# gforce_single_board.net
KiCad netlist of a schematic drawn in EAGLE
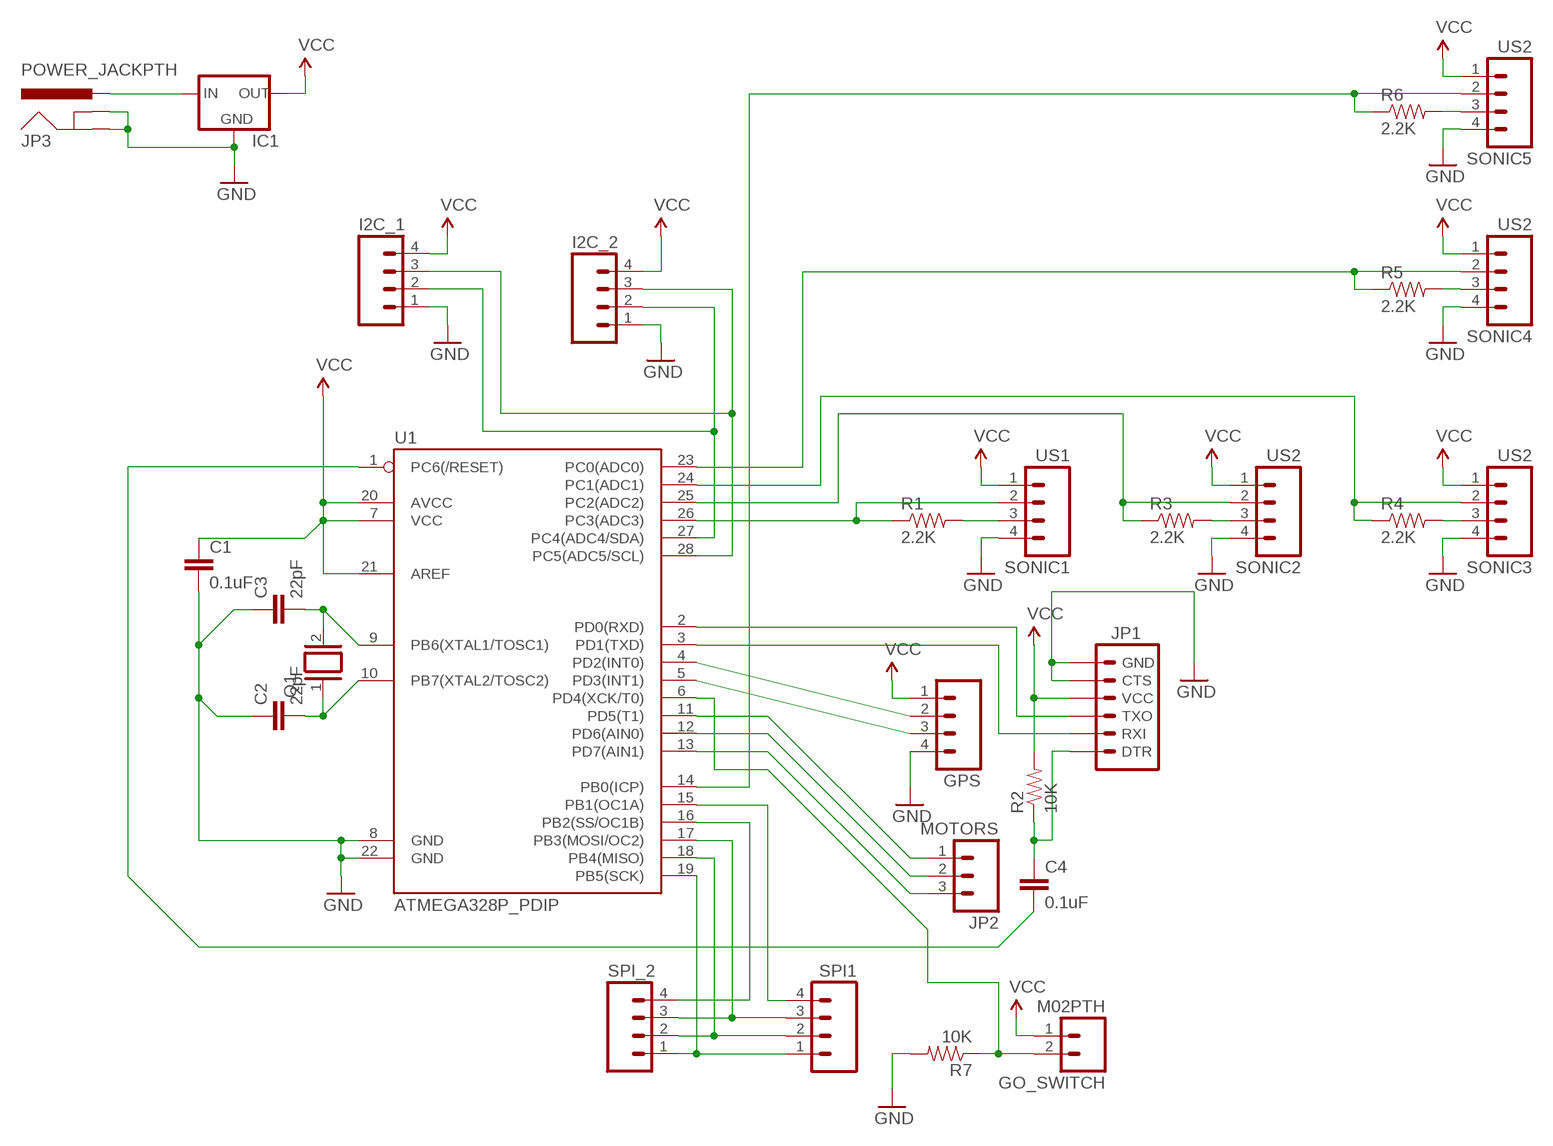
[diagram p0: schematic, sheet 1]

(export (version "E")
  (design (tool "Eeschema 10.0.6"))
  (components
    (comp (ref "C1")
      (value "0.1uF")
      (footprint "eagle-import:CAP-PTH-SMALL")
      (libsource (lib "eagle-import") (part "CAPPTH"))
    )
    (comp (ref "C2")
      (value "22pF")
      (footprint "eagle-import:CAP-PTH-SMALL")
      (libsource (lib "eagle-import") (part "CAPPTH"))
    )
    (comp (ref "C3")
      (value "22pF")
      (footprint "eagle-import:CAP-PTH-SMALL")
      (libsource (lib "eagle-import") (part "CAPPTH"))
    )
    (comp (ref "C4")
      (value "0.1uF")
      (footprint "eagle-import:CAP-PTH-SMALL")
      (libsource (lib "eagle-import") (part "CAPPTH"))
    )
    (comp (ref "GO_SWITCH")
      (value "M02PTH")
      (footprint "eagle-import:1X02")
      (libsource (lib "eagle-import") (part "M02PTH"))
    )
    (comp (ref "GPS")
      (value "M04PTH")
      (footprint "eagle-import:1X04")
      (libsource (lib "eagle-import") (part "M04PTH"))
    )
    (comp (ref "I2C_1")
      (value "M04PTH")
      (footprint "eagle-import:1X04")
      (libsource (lib "eagle-import") (part "M04PTH"))
    )
    (comp (ref "I2C_2")
      (value "M04PTH")
      (footprint "eagle-import:1X04")
      (libsource (lib "eagle-import") (part "M04PTH"))
    )
    (comp (ref "IC1")
      (value "V_REG_78XX-TO-220")
      (footprint "eagle-import:TO-220-ALT")
      (libsource (lib "eagle-import") (part "V_REG_78XX-TO-220"))
    )
    (comp (ref "JP1")
      (value "ARDUINO_SERIAL_PROGRAMPTH")
      (footprint "eagle-import:1X06")
      (libsource (lib "eagle-import") (part "ARDUINO_SERIAL_PROGRAMPTH"))
    )
    (comp (ref "JP2")
      (value "MOTORS")
      (footprint "eagle-import:1X03")
      (libsource (lib "eagle-import") (part "M03PTH"))
    )
    (comp (ref "JP3")
      (value "POWER_JACKPTH")
      (footprint "eagle-import:POWER_JACK_PTH")
      (libsource (lib "eagle-import") (part "POWER_JACKPTH"))
    )
    (comp (ref "Q1")
      (value "XTAL/S")
      (footprint "eagle-import:QS")
      (libsource (lib "eagle-import") (part "XTAL/S"))
    )
    (comp (ref "R1")
      (value "2.2K")
      (footprint "eagle-import:AXIAL-0.4")
      (libsource (lib "eagle-import") (part "RESISTORPTH-1/4W"))
    )
    (comp (ref "R2")
      (value "10K")
      (footprint "eagle-import:AXIAL-0.4")
      (libsource (lib "eagle-import") (part "RESISTORPTH-1/4W"))
    )
    (comp (ref "R3")
      (value "2.2K")
      (footprint "eagle-import:AXIAL-0.4")
      (libsource (lib "eagle-import") (part "RESISTORPTH-1/4W"))
    )
    (comp (ref "R4")
      (value "2.2K")
      (footprint "eagle-import:AXIAL-0.4")
      (libsource (lib "eagle-import") (part "RESISTORPTH-1/4W"))
    )
    (comp (ref "R5")
      (value "2.2K")
      (footprint "eagle-import:AXIAL-0.4")
      (libsource (lib "eagle-import") (part "RESISTORPTH-1/4W"))
    )
    (comp (ref "R6")
      (value "2.2K")
      (footprint "eagle-import:AXIAL-0.4")
      (libsource (lib "eagle-import") (part "RESISTORPTH-1/4W"))
    )
    (comp (ref "R7")
      (value "10K")
      (footprint "eagle-import:AXIAL-0.4")
      (libsource (lib "eagle-import") (part "RESISTORPTH-1/4W"))
    )
    (comp (ref "SONIC1")
      (value "US1")
      (footprint "eagle-import:1X04")
      (libsource (lib "eagle-import") (part "M04PTH"))
    )
    (comp (ref "SONIC2")
      (value "US2")
      (footprint "eagle-import:1X04")
      (libsource (lib "eagle-import") (part "M04PTH"))
    )
    (comp (ref "SONIC3")
      (value "US2")
      (footprint "eagle-import:1X04")
      (libsource (lib "eagle-import") (part "M04PTH"))
    )
    (comp (ref "SONIC4")
      (value "US2")
      (footprint "eagle-import:1X04")
      (libsource (lib "eagle-import") (part "M04PTH"))
    )
    (comp (ref "SONIC5")
      (value "US2")
      (footprint "eagle-import:1X04")
      (libsource (lib "eagle-import") (part "M04PTH"))
    )
    (comp (ref "SPI1")
      (value "M04PTH")
      (footprint "eagle-import:1X04")
      (libsource (lib "eagle-import") (part "M04PTH"))
    )
    (comp (ref "SPI_2")
      (value "M04PTH")
      (footprint "eagle-import:1X04")
      (libsource (lib "eagle-import") (part "M04PTH"))
    )
    (comp (ref "U1")
      (value "ATMEGA328P_PDIP")
      (footprint "eagle-import:DIL28-3")
      (libsource (lib "eagle-import") (part "ATMEGA328P_PDIP"))
    )
  )
  (nets
    (net (code "1") (name "GND") (class "Default")
      (node (ref "C1") (pin "2") (pinfunction "2_2") (pintype "passive"))
      (node (ref "C2") (pin "1") (pinfunction "1_1") (pintype "passive"))
      (node (ref "C3") (pin "1") (pinfunction "1_1") (pintype "passive"))
      (node (ref "GPS") (pin "4") (pinfunction "4_4") (pintype "passive"))
      (node (ref "I2C_1") (pin "1") (pinfunction "1_1") (pintype "passive"))
      (node (ref "I2C_2") (pin "1") (pinfunction "1_1") (pintype "passive"))
      (node (ref "IC1") (pin "GND") (pinfunction "GND_GND") (pintype "input"))
      (node (ref "JP1") (pin "5") (pinfunction "CTS_5") (pintype "passive"))
      (node (ref "JP1") (pin "6") (pinfunction "GND_6") (pintype "passive"))
      (node (ref "JP3") (pin "GND") (pinfunction "GND_GND") (pintype "bidirectional"))
      (node (ref "JP3") (pin "GNDBREAK") (pinfunction "GNDBREAK_GNDBREAK") (pintype "bidirectional"))
      (node (ref "R7") (pin "P$2") (pinfunction "2_P$2") (pintype "passive"))
      (node (ref "SONIC1") (pin "4") (pinfunction "4_4") (pintype "passive"))
      (node (ref "SONIC2") (pin "4") (pinfunction "4_4") (pintype "passive"))
      (node (ref "SONIC3") (pin "4") (pinfunction "4_4") (pintype "passive"))
      (node (ref "SONIC4") (pin "4") (pinfunction "4_4") (pintype "passive"))
      (node (ref "SONIC5") (pin "4") (pinfunction "4_4") (pintype "passive"))
      (node (ref "U1") (pin "22") (pinfunction "GND_22") (pintype "bidirectional"))
      (node (ref "U1") (pin "8") (pinfunction "GND_8") (pintype "bidirectional"))
    )
    (net (code "2") (name "Net-(IC1-PadIN)") (class "Default")
      (node (ref "IC1") (pin "IN") (pinfunction "IN_IN") (pintype "input"))
      (node (ref "JP3") (pin "PWR") (pinfunction "PWR_PWR") (pintype "bidirectional"))
    )
    (net (code "3") (name "Net-(JP1-DTR)") (class "Default")
      (node (ref "C4") (pin "1") (pinfunction "1_1") (pintype "passive"))
      (node (ref "JP1") (pin "1") (pinfunction "DTR_1") (pintype "passive"))
      (node (ref "R2") (pin "P$1") (pinfunction "1_P$1") (pintype "passive"))
    )
    (net (code "4") (name "Net-(JP1-RXI)") (class "Default")
      (node (ref "JP1") (pin "2") (pinfunction "RXI_2") (pintype "passive"))
      (node (ref "U1") (pin "3") (pinfunction "PD1(TXD)_3") (pintype "bidirectional"))
    )
    (net (code "5") (name "Net-(JP1-TXO)") (class "Default")
      (node (ref "JP1") (pin "3") (pinfunction "TXO_3") (pintype "passive"))
      (node (ref "U1") (pin "2") (pinfunction "PD0(RXD)_2") (pintype "bidirectional"))
    )
    (net (code "6") (name "Net-(R1-1)") (class "Default")
      (node (ref "R1") (pin "P$1") (pinfunction "1_P$1") (pintype "passive"))
      (node (ref "SONIC1") (pin "2") (pinfunction "2_2") (pintype "passive"))
      (node (ref "U1") (pin "26") (pinfunction "PC3(ADC3)_26") (pintype "bidirectional"))
    )
    (net (code "7") (name "Net-(R1-2)") (class "Default")
      (node (ref "R1") (pin "P$2") (pinfunction "2_P$2") (pintype "passive"))
      (node (ref "SONIC1") (pin "3") (pinfunction "3_3") (pintype "passive"))
    )
    (net (code "8") (name "Net-(R3-1)") (class "Default")
      (node (ref "R3") (pin "P$1") (pinfunction "1_P$1") (pintype "passive"))
      (node (ref "SONIC2") (pin "2") (pinfunction "2_2") (pintype "passive"))
      (node (ref "U1") (pin "25") (pinfunction "PC2(ADC2)_25") (pintype "bidirectional"))
    )
    (net (code "9") (name "Net-(R3-2)") (class "Default")
      (node (ref "R3") (pin "P$2") (pinfunction "2_P$2") (pintype "passive"))
      (node (ref "SONIC2") (pin "3") (pinfunction "3_3") (pintype "passive"))
    )
    (net (code "10") (name "Net-(R4-1)") (class "Default")
      (node (ref "R4") (pin "P$1") (pinfunction "1_P$1") (pintype "passive"))
      (node (ref "SONIC3") (pin "2") (pinfunction "2_2") (pintype "passive"))
      (node (ref "U1") (pin "24") (pinfunction "PC1(ADC1)_24") (pintype "bidirectional"))
    )
    (net (code "11") (name "Net-(R4-2)") (class "Default")
      (node (ref "R4") (pin "P$2") (pinfunction "2_P$2") (pintype "passive"))
      (node (ref "SONIC3") (pin "3") (pinfunction "3_3") (pintype "passive"))
    )
    (net (code "12") (name "Net-(R5-1)") (class "Default")
      (node (ref "R5") (pin "P$1") (pinfunction "1_P$1") (pintype "passive"))
      (node (ref "SONIC4") (pin "2") (pinfunction "2_2") (pintype "passive"))
      (node (ref "U1") (pin "23") (pinfunction "PC0(ADC0)_23") (pintype "bidirectional"))
    )
    (net (code "13") (name "Net-(R5-2)") (class "Default")
      (node (ref "R5") (pin "P$2") (pinfunction "2_P$2") (pintype "passive"))
      (node (ref "SONIC4") (pin "3") (pinfunction "3_3") (pintype "passive"))
    )
    (net (code "14") (name "Net-(R6-1)") (class "Default")
      (node (ref "R6") (pin "P$1") (pinfunction "1_P$1") (pintype "passive"))
      (node (ref "SONIC5") (pin "2") (pinfunction "2_2") (pintype "passive"))
      (node (ref "U1") (pin "14") (pinfunction "PB0(ICP)_14") (pintype "bidirectional"))
    )
    (net (code "15") (name "Net-(R6-2)") (class "Default")
      (node (ref "R6") (pin "P$2") (pinfunction "2_P$2") (pintype "passive"))
      (node (ref "SONIC5") (pin "3") (pinfunction "3_3") (pintype "passive"))
    )
    (net (code "16") (name "Net-(R7-1)") (class "Default")
      (node (ref "GO_SWITCH") (pin "2") (pinfunction "2_2") (pintype "passive"))
      (node (ref "R7") (pin "P$1") (pinfunction "1_P$1") (pintype "passive"))
      (node (ref "U1") (pin "6") (pinfunction "PD4(XCK/T0)_6") (pintype "bidirectional"))
    )
    (net (code "17") (name "Net-(U1-PB1(OC1A))") (class "Default")
      (node (ref "SPI1") (pin "4") (pinfunction "4_4") (pintype "passive"))
      (node (ref "U1") (pin "15") (pinfunction "PB1(OC1A)_15") (pintype "bidirectional"))
    )
    (net (code "18") (name "Net-(U1-PB2(SS{slash}OC1B))") (class "Default")
      (node (ref "SPI_2") (pin "4") (pinfunction "4_4") (pintype "passive"))
      (node (ref "U1") (pin "16") (pinfunction "PB2(SS/OC1B)_16") (pintype "bidirectional"))
    )
    (net (code "19") (name "Net-(U1-PB3(MOSI{slash}OC2))") (class "Default")
      (node (ref "SPI1") (pin "3") (pinfunction "3_3") (pintype "passive"))
      (node (ref "SPI_2") (pin "3") (pinfunction "3_3") (pintype "passive"))
      (node (ref "U1") (pin "17") (pinfunction "PB3(MOSI/OC2)_17") (pintype "bidirectional"))
    )
    (net (code "20") (name "Net-(U1-PB4(MISO))") (class "Default")
      (node (ref "SPI1") (pin "2") (pinfunction "2_2") (pintype "passive"))
      (node (ref "SPI_2") (pin "2") (pinfunction "2_2") (pintype "passive"))
      (node (ref "U1") (pin "18") (pinfunction "PB4(MISO)_18") (pintype "bidirectional"))
    )
    (net (code "21") (name "Net-(U1-PB5(SCK))") (class "Default")
      (node (ref "SPI1") (pin "1") (pinfunction "1_1") (pintype "passive"))
      (node (ref "SPI_2") (pin "1") (pinfunction "1_1") (pintype "passive"))
      (node (ref "U1") (pin "19") (pinfunction "PB5(SCK)_19") (pintype "bidirectional"))
    )
    (net (code "22") (name "Net-(U1-PB6(XTAL1{slash}TOSC1))") (class "Default")
      (node (ref "C3") (pin "2") (pinfunction "2_2") (pintype "passive"))
      (node (ref "Q1") (pin "2") (pinfunction "2_2") (pintype "passive"))
      (node (ref "U1") (pin "9") (pinfunction "PB6(XTAL1/TOSC1)_9") (pintype "bidirectional"))
    )
    (net (code "23") (name "Net-(U1-PB7(XTAL2{slash}TOSC2))") (class "Default")
      (node (ref "C2") (pin "2") (pinfunction "2_2") (pintype "passive"))
      (node (ref "Q1") (pin "1") (pinfunction "1_1") (pintype "passive"))
      (node (ref "U1") (pin "10") (pinfunction "PB7(XTAL2/TOSC2)_10") (pintype "bidirectional"))
    )
    (net (code "24") (name "Net-(U1-PC4(ADC4{slash}SDA))") (class "Default")
      (node (ref "I2C_1") (pin "2") (pinfunction "2_2") (pintype "passive"))
      (node (ref "I2C_2") (pin "2") (pinfunction "2_2") (pintype "passive"))
      (node (ref "U1") (pin "27") (pinfunction "PC4(ADC4/SDA)_27") (pintype "bidirectional"))
    )
    (net (code "25") (name "Net-(U1-PC5(ADC5{slash}SCL))") (class "Default")
      (node (ref "I2C_1") (pin "3") (pinfunction "3_3") (pintype "passive"))
      (node (ref "I2C_2") (pin "3") (pinfunction "3_3") (pintype "passive"))
      (node (ref "U1") (pin "28") (pinfunction "PC5(ADC5/SCL)_28") (pintype "bidirectional"))
    )
    (net (code "26") (name "Net-(U1-PC6({slash}RESET))") (class "Default")
      (node (ref "C4") (pin "2") (pinfunction "2_2") (pintype "passive"))
      (node (ref "U1") (pin "1") (pinfunction "PC6(/RESET)_1") (pintype "bidirectional"))
    )
    (net (code "27") (name "Net-(U1-PD2(INT0))") (class "Default")
      (node (ref "GPS") (pin "2") (pinfunction "2_2") (pintype "passive"))
      (node (ref "U1") (pin "4") (pinfunction "PD2(INT0)_4") (pintype "bidirectional"))
    )
    (net (code "28") (name "Net-(U1-PD3(INT1))") (class "Default")
      (node (ref "GPS") (pin "3") (pinfunction "3_3") (pintype "passive"))
      (node (ref "U1") (pin "5") (pinfunction "PD3(INT1)_5") (pintype "bidirectional"))
    )
    (net (code "29") (name "Net-(U1-PD5(T1))") (class "Default")
      (node (ref "JP2") (pin "1") (pinfunction "1_1") (pintype "passive"))
      (node (ref "U1") (pin "11") (pinfunction "PD5(T1)_11") (pintype "bidirectional"))
    )
    (net (code "30") (name "Net-(U1-PD6(AIN0))") (class "Default")
      (node (ref "JP2") (pin "2") (pinfunction "2_2") (pintype "passive"))
      (node (ref "U1") (pin "12") (pinfunction "PD6(AIN0)_12") (pintype "bidirectional"))
    )
    (net (code "31") (name "Net-(U1-PD7(AIN1))") (class "Default")
      (node (ref "JP2") (pin "3") (pinfunction "3_3") (pintype "passive"))
      (node (ref "U1") (pin "13") (pinfunction "PD7(AIN1)_13") (pintype "bidirectional"))
    )
    (net (code "32") (name "VCC") (class "Default")
      (node (ref "C1") (pin "1") (pinfunction "1_1") (pintype "passive"))
      (node (ref "GO_SWITCH") (pin "1") (pinfunction "1_1") (pintype "passive"))
      (node (ref "GPS") (pin "1") (pinfunction "1_1") (pintype "passive"))
      (node (ref "I2C_1") (pin "4") (pinfunction "4_4") (pintype "passive"))
      (node (ref "I2C_2") (pin "4") (pinfunction "4_4") (pintype "passive"))
      (node (ref "IC1") (pin "OUT") (pinfunction "OUT_OUT") (pintype "output"))
      (node (ref "JP1") (pin "4") (pinfunction "VCC_4") (pintype "passive"))
      (node (ref "R2") (pin "P$2") (pinfunction "2_P$2") (pintype "passive"))
      (node (ref "SONIC1") (pin "1") (pinfunction "1_1") (pintype "passive"))
      (node (ref "SONIC2") (pin "1") (pinfunction "1_1") (pintype "passive"))
      (node (ref "SONIC3") (pin "1") (pinfunction "1_1") (pintype "passive"))
      (node (ref "SONIC4") (pin "1") (pinfunction "1_1") (pintype "passive"))
      (node (ref "SONIC5") (pin "1") (pinfunction "1_1") (pintype "passive"))
      (node (ref "U1") (pin "20") (pinfunction "AVCC_20") (pintype "bidirectional"))
      (node (ref "U1") (pin "21") (pinfunction "AREF_21") (pintype "bidirectional"))
      (node (ref "U1") (pin "7") (pinfunction "VCC_7") (pintype "bidirectional"))
    )
  )
)
